# chlorophyll_analyzer_LEDs.net
KiCad netlist of a schematic drawn in EAGLE
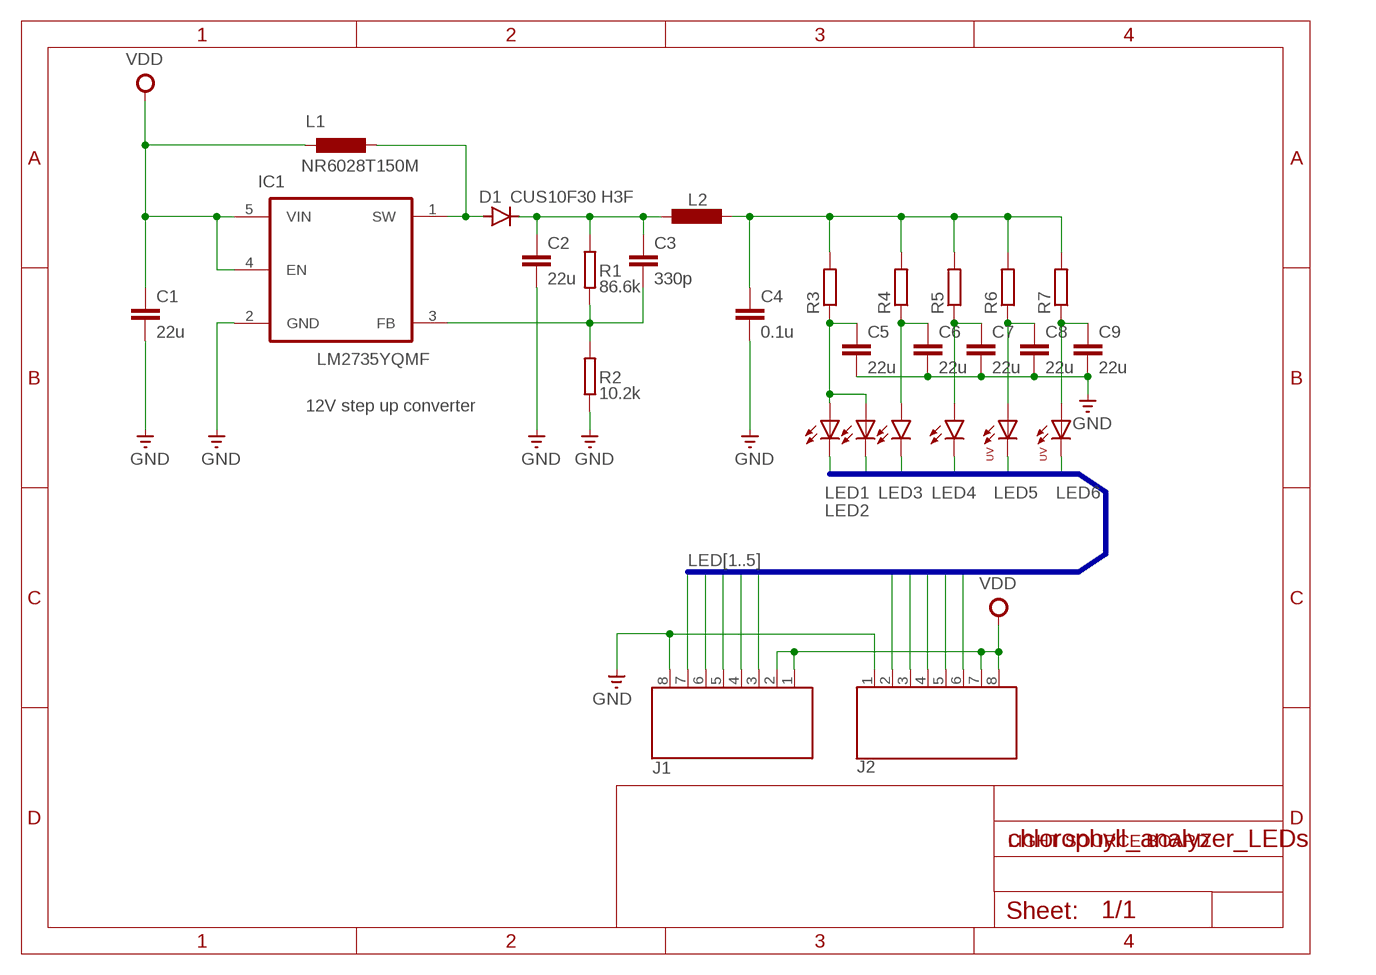
[diagram p0: schematic, sheet 1]

(export (version "E")
  (design (tool "Eeschema 10.0.6"))
  (components
    (comp (ref "C1")
      (value "22u")
      (footprint "eagle-import:C0603K")
      (libsource (lib "eagle-import") (part "C-EUC0603K"))
    )
    (comp (ref "C2")
      (value "22u")
      (footprint "eagle-import:C0603K")
      (libsource (lib "eagle-import") (part "C-EUC0603K"))
    )
    (comp (ref "C3")
      (value "330p")
      (footprint "eagle-import:C0603K")
      (libsource (lib "eagle-import") (part "C-EUC0603K"))
    )
    (comp (ref "C4")
      (value "0.1u")
      (footprint "eagle-import:C0603K")
      (libsource (lib "eagle-import") (part "C-EUC0603K"))
    )
    (comp (ref "C5")
      (value "22u")
      (footprint "eagle-import:C0603K")
      (libsource (lib "eagle-import") (part "C-EUC0603K"))
    )
    (comp (ref "C6")
      (value "22u")
      (footprint "eagle-import:C0603K")
      (libsource (lib "eagle-import") (part "C-EUC0603K"))
    )
    (comp (ref "C7")
      (value "22u")
      (footprint "eagle-import:C0603K")
      (libsource (lib "eagle-import") (part "C-EUC0603K"))
    )
    (comp (ref "C8")
      (value "22u")
      (footprint "eagle-import:C0603K")
      (libsource (lib "eagle-import") (part "C-EUC0603K"))
    )
    (comp (ref "C9")
      (value "22u")
      (footprint "eagle-import:C0603K")
      (libsource (lib "eagle-import") (part "C-EUC0603K"))
    )
    (comp (ref "D1")
      (value "CUS10F30 H3F")
      (footprint "eagle-import:SOD323-W")
      (libsource (lib "eagle-import") (part "DIODE-SOD323-W"))
    )
    (comp (ref "IC1")
      (value "LM2735YQMF")
      (footprint "eagle-import:SOT65P285X120-5N")
      (fields (field (name "MF") "Texas Instruments") (field (name "MP") "LM2735YQMF/NOPB"))
      (libsource (lib "eagle-import") (part "LM2735YQMF"))
    )
    (comp (ref "J1")
      (value "687108183722")
      (footprint "eagle-import:687108183722")
      (libsource (lib "eagle-import") (part "687108183722"))
    )
    (comp (ref "J2")
      (value "687108183722")
      (footprint "eagle-import:687108183722")
      (libsource (lib "eagle-import") (part "687108183722"))
    )
    (comp (ref "L1")
      (value "NR6028T150M")
      (footprint "eagle-import:IND_TAIYO_NR6028")
      (libsource (lib "eagle-import") (part "NR6028T150M"))
    )
    (comp (ref "L2")
      (value "INDUCOR2012")
      (footprint "eagle-import:SMD2012")
      (libsource (lib "eagle-import") (part "INDUCOR2012"))
    )
    (comp (ref "LED1")
      (value "L130-S1S0-3030509506-0000003S-000015080003000W21")
      (footprint "eagle-import:LED_L130-5080003000W21")
      (fields (field (name "MF") "Lumileds") (field (name "MP") "L130-5080003000W21"))
      (libsource (lib "eagle-import") (part "L130-5080003000W21"))
    )
    (comp (ref "LED2")
      (value "L130-S1S0-3030509506-0000003S-000015080003000W21")
      (footprint "eagle-import:LED_L130-5080003000W21")
      (fields (field (name "MF") "Lumileds") (field (name "MP") "L130-5080003000W21"))
      (libsource (lib "eagle-import") (part "L130-5080003000W21"))
    )
    (comp (ref "LED3")
      (value "LEDCHIPLED_1206")
      (footprint "eagle-import:CHIPLED_1206")
      (libsource (lib "eagle-import") (part "LEDCHIPLED_1206"))
    )
    (comp (ref "LED4")
      (value "LEDCHIPLED_1206")
      (footprint "eagle-import:CHIPLED_1206")
      (libsource (lib "eagle-import") (part "LEDCHIPLED_1206"))
    )
    (comp (ref "LED5")
      (value "ELUA2016OGB-P8090Q53038020-VA1M")
      (footprint "eagle-import:ELUA2016OGB0.08")
      (libsource (lib "eagle-import") (part "ELUA2016OGB"))
    )
    (comp (ref "LED6")
      (value "ELUA2016OGB-P8090Q53038020-VA1M")
      (footprint "eagle-import:ELUA2016OGB0.08")
      (libsource (lib "eagle-import") (part "ELUA2016OGB"))
    )
    (comp (ref "R1")
      (value "86.6k")
      (footprint "eagle-import:SMD1608")
      (libsource (lib "eagle-import") (part "RESISTOR1608"))
    )
    (comp (ref "R2")
      (value "10.2k")
      (footprint "eagle-import:SMD1608")
      (libsource (lib "eagle-import") (part "RESISTOR1608"))
    )
    (comp (ref "R3")
      (value "R-EU_R0805")
      (footprint "eagle-import:R0805")
      (libsource (lib "eagle-import") (part "R-EU_R0805"))
    )
    (comp (ref "R4")
      (value "R-EU_R0805")
      (footprint "eagle-import:R0805")
      (libsource (lib "eagle-import") (part "R-EU_R0805"))
    )
    (comp (ref "R5")
      (value "R-EU_R0805")
      (footprint "eagle-import:R0805")
      (libsource (lib "eagle-import") (part "R-EU_R0805"))
    )
    (comp (ref "R6")
      (value "R-EU_R0805")
      (footprint "eagle-import:R0805")
      (libsource (lib "eagle-import") (part "R-EU_R0805"))
    )
    (comp (ref "R7")
      (value "R-EU_R0805")
      (footprint "eagle-import:R0805")
      (libsource (lib "eagle-import") (part "R-EU_R0805"))
    )
  )
  (nets
    (net (code "1") (name "/LED1") (class "Default")
      (node (ref "J1") (pin "3") (pinfunction "6_3") (pintype "passive"))
      (node (ref "J2") (pin "6") (pinfunction "3_6") (pintype "passive"))
      (node (ref "LED1") (pin "C") (pinfunction "C_C") (pintype "passive"))
      (node (ref "LED2") (pin "C") (pinfunction "C_C") (pintype "passive"))
    )
    (net (code "2") (name "/LED2") (class "Default")
      (node (ref "J1") (pin "4") (pinfunction "5_4") (pintype "passive"))
      (node (ref "J2") (pin "5") (pinfunction "4_5") (pintype "passive"))
      (node (ref "LED3") (pin "C") (pinfunction "C_C") (pintype "passive"))
    )
    (net (code "3") (name "/LED3") (class "Default")
      (node (ref "J1") (pin "5") (pinfunction "4_5") (pintype "passive"))
      (node (ref "LED4") (pin "C") (pinfunction "C_C") (pintype "passive"))
    )
    (net (code "4") (name "/LED4") (class "Default")
      (node (ref "J1") (pin "6") (pinfunction "3_6") (pintype "passive"))
      (node (ref "J2") (pin "3") (pinfunction "6_3") (pintype "passive"))
      (node (ref "J2") (pin "4") (pinfunction "5_4") (pintype "passive"))
      (node (ref "LED5") (pin "C") (pinfunction "C1_C") (pintype "passive"))
    )
    (net (code "5") (name "/LED5") (class "Default")
      (node (ref "J1") (pin "7") (pinfunction "2_7") (pintype "passive"))
      (node (ref "J2") (pin "2") (pinfunction "7_2") (pintype "passive"))
      (node (ref "LED6") (pin "C") (pinfunction "C1_C") (pintype "passive"))
    )
    (net (code "7") (name "GND") (class "Default")
      (node (ref "C1") (pin "2") (pinfunction "2_2") (pintype "passive"))
      (node (ref "C2") (pin "2") (pinfunction "2_2") (pintype "passive"))
      (node (ref "C4") (pin "2") (pinfunction "2_2") (pintype "passive"))
      (node (ref "C5") (pin "2") (pinfunction "2_2") (pintype "passive"))
      (node (ref "C6") (pin "2") (pinfunction "2_2") (pintype "passive"))
      (node (ref "C7") (pin "2") (pinfunction "2_2") (pintype "passive"))
      (node (ref "C8") (pin "2") (pinfunction "2_2") (pintype "passive"))
      (node (ref "C9") (pin "2") (pinfunction "2_2") (pintype "passive"))
      (node (ref "IC1") (pin "2") (pinfunction "GND_2") (pintype "passive"))
      (node (ref "J1") (pin "8") (pinfunction "1_8") (pintype "passive"))
      (node (ref "J2") (pin "1") (pinfunction "8_1") (pintype "passive"))
      (node (ref "R2") (pin "1") (pinfunction "1_1") (pintype "passive"))
    )
    (net (code "8") (name "Net-(C2-Pad1)") (class "Default")
      (node (ref "C2") (pin "1") (pinfunction "1_1") (pintype "passive"))
      (node (ref "C3") (pin "1") (pinfunction "1_1") (pintype "passive"))
      (node (ref "D1") (pin "C") (pinfunction "C_C") (pintype "passive"))
      (node (ref "L2") (pin "2") (pinfunction "2_2") (pintype "passive"))
      (node (ref "R1") (pin "2") (pinfunction "2_2") (pintype "passive"))
    )
    (net (code "9") (name "Net-(C4-Pad1)") (class "Default")
      (node (ref "C4") (pin "1") (pinfunction "1_1") (pintype "passive"))
      (node (ref "L2") (pin "1") (pinfunction "1_1") (pintype "passive"))
      (node (ref "R3") (pin "2") (pinfunction "2_2") (pintype "passive"))
      (node (ref "R4") (pin "2") (pinfunction "2_2") (pintype "passive"))
      (node (ref "R5") (pin "2") (pinfunction "2_2") (pintype "passive"))
      (node (ref "R6") (pin "2") (pinfunction "2_2") (pintype "passive"))
      (node (ref "R7") (pin "2") (pinfunction "2_2") (pintype "passive"))
    )
    (net (code "10") (name "Net-(C5-Pad1)") (class "Default")
      (node (ref "C5") (pin "1") (pinfunction "1_1") (pintype "passive"))
      (node (ref "LED1") (pin "A") (pinfunction "A_A") (pintype "passive"))
      (node (ref "LED2") (pin "A") (pinfunction "A_A") (pintype "passive"))
      (node (ref "R3") (pin "1") (pinfunction "1_1") (pintype "passive"))
    )
    (net (code "11") (name "Net-(C6-Pad1)") (class "Default")
      (node (ref "C6") (pin "1") (pinfunction "1_1") (pintype "passive"))
      (node (ref "LED3") (pin "A") (pinfunction "A_A") (pintype "passive"))
      (node (ref "R4") (pin "1") (pinfunction "1_1") (pintype "passive"))
    )
    (net (code "12") (name "Net-(C7-Pad1)") (class "Default")
      (node (ref "C7") (pin "1") (pinfunction "1_1") (pintype "passive"))
      (node (ref "LED4") (pin "A") (pinfunction "A_A") (pintype "passive"))
      (node (ref "R5") (pin "1") (pinfunction "1_1") (pintype "passive"))
    )
    (net (code "13") (name "Net-(IC1-FB)") (class "Default")
      (node (ref "C3") (pin "2") (pinfunction "2_2") (pintype "passive"))
      (node (ref "IC1") (pin "3") (pinfunction "FB_3") (pintype "input"))
      (node (ref "R1") (pin "1") (pinfunction "1_1") (pintype "passive"))
      (node (ref "R2") (pin "2") (pinfunction "2_2") (pintype "passive"))
    )
    (net (code "14") (name "Net-(IC1-SW)") (class "Default")
      (node (ref "D1") (pin "A") (pinfunction "A_A") (pintype "passive"))
      (node (ref "IC1") (pin "1") (pinfunction "SW_1") (pintype "output"))
      (node (ref "L1") (pin "1") (pinfunction "1_1") (pintype "passive"))
    )
    (net (code "15") (name "Net-(LED5-A1)") (class "Default")
      (node (ref "C8") (pin "1") (pinfunction "1_1") (pintype "passive"))
      (node (ref "LED5") (pin "A") (pinfunction "A1_A") (pintype "passive"))
      (node (ref "R6") (pin "1") (pinfunction "1_1") (pintype "passive"))
    )
    (net (code "16") (name "Net-(LED6-A1)") (class "Default")
      (node (ref "C9") (pin "1") (pinfunction "1_1") (pintype "passive"))
      (node (ref "LED6") (pin "A") (pinfunction "A1_A") (pintype "passive"))
      (node (ref "R7") (pin "1") (pinfunction "1_1") (pintype "passive"))
    )
    (net (code "17") (name "VDD") (class "Default")
      (node (ref "C1") (pin "1") (pinfunction "1_1") (pintype "passive"))
      (node (ref "IC1") (pin "4") (pinfunction "EN_4") (pintype "input"))
      (node (ref "IC1") (pin "5") (pinfunction "VIN_5") (pintype "power_in"))
      (node (ref "J1") (pin "1") (pinfunction "8_1") (pintype "passive"))
      (node (ref "J1") (pin "2") (pinfunction "7_2") (pintype "passive"))
      (node (ref "J2") (pin "7") (pinfunction "2_7") (pintype "passive"))
      (node (ref "J2") (pin "8") (pinfunction "1_8") (pintype "passive"))
      (node (ref "L1") (pin "2") (pinfunction "2_2") (pintype "passive"))
    )
  )
)
